# Main_module_scheme.net
KiCad netlist of a schematic drawn in EAGLE
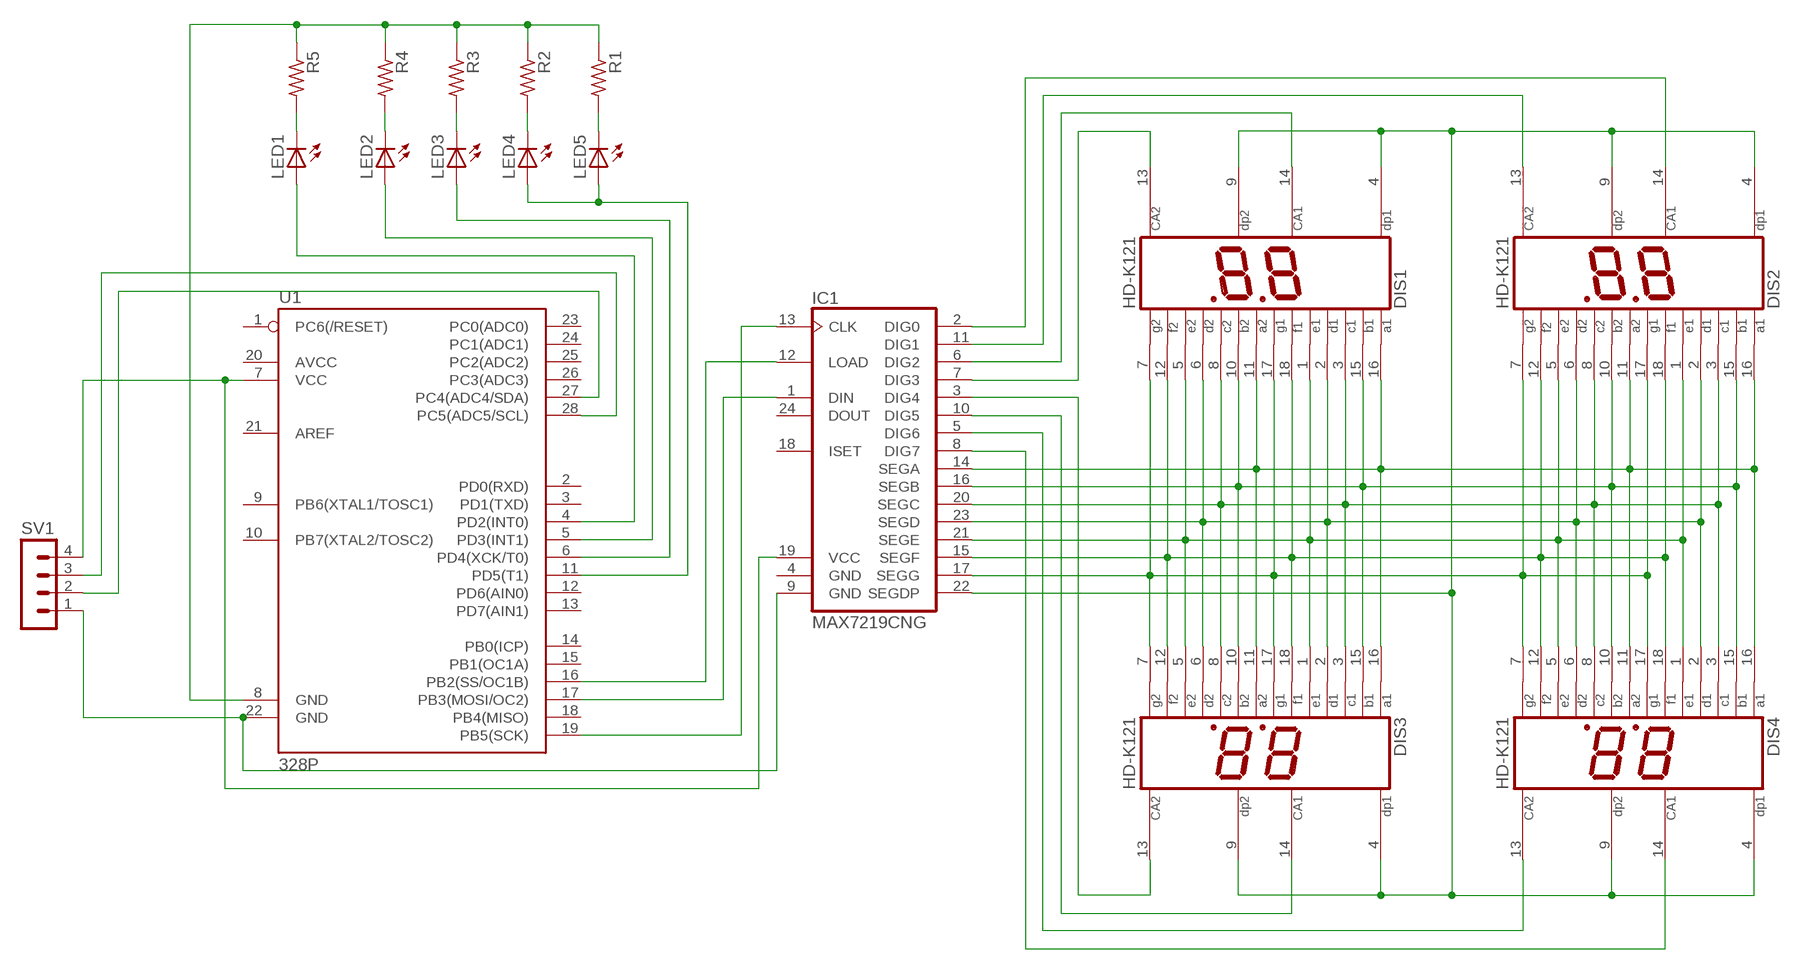
[diagram p0: schematic, sheet 1]

(export (version "E")
  (design (tool "Eeschema 10.0.6"))
  (components
    (comp (ref "DIS1")
      (value "HD-K121")
      (footprint "eagle-import:HDSP-R")
      (libsource (lib "eagle-import") (part "HD-K121"))
    )
    (comp (ref "DIS2")
      (value "HD-K121")
      (footprint "eagle-import:HDSP-R")
      (libsource (lib "eagle-import") (part "HD-K121"))
    )
    (comp (ref "DIS3")
      (value "HD-K121")
      (footprint "eagle-import:HDSP-R")
      (libsource (lib "eagle-import") (part "HD-K121"))
    )
    (comp (ref "DIS4")
      (value "HD-K121")
      (footprint "eagle-import:HDSP-R")
      (libsource (lib "eagle-import") (part "HD-K121"))
    )
    (comp (ref "IC1")
      (value "MAX7219CNG")
      (footprint "eagle-import:DIL24-3")
      (fields (field (name "MF") "MAXIM"))
      (libsource (lib "eagle-import") (part "MAX7219CNG"))
    )
    (comp (ref "LED1")
      (value "LED5MM")
      (footprint "eagle-import:LED5MM")
      (libsource (lib "eagle-import") (part "LED5MM"))
    )
    (comp (ref "LED2")
      (value "LED5MM")
      (footprint "eagle-import:LED5MM")
      (libsource (lib "eagle-import") (part "LED5MM"))
    )
    (comp (ref "LED3")
      (value "LED5MM")
      (footprint "eagle-import:LED5MM")
      (libsource (lib "eagle-import") (part "LED5MM"))
    )
    (comp (ref "LED4")
      (value "LED5MM")
      (footprint "eagle-import:LED5MM")
      (libsource (lib "eagle-import") (part "LED5MM"))
    )
    (comp (ref "LED5")
      (value "LED5MM")
      (footprint "eagle-import:LED5MM")
      (libsource (lib "eagle-import") (part "LED5MM"))
    )
    (comp (ref "R1")
      (value "FLIPFLOP-RES")
      (footprint "eagle-import:0805-THM")
      (libsource (lib "eagle-import") (part "FLIPFLOP-RES"))
    )
    (comp (ref "R2")
      (value "FLIPFLOP-RES")
      (footprint "eagle-import:0805-THM")
      (libsource (lib "eagle-import") (part "FLIPFLOP-RES"))
    )
    (comp (ref "R3")
      (value "FLIPFLOP-RES")
      (footprint "eagle-import:0805-THM")
      (libsource (lib "eagle-import") (part "FLIPFLOP-RES"))
    )
    (comp (ref "R4")
      (value "FLIPFLOP-RES")
      (footprint "eagle-import:0805-THM")
      (libsource (lib "eagle-import") (part "FLIPFLOP-RES"))
    )
    (comp (ref "R5")
      (value "FLIPFLOP-RES")
      (footprint "eagle-import:0805-THM")
      (libsource (lib "eagle-import") (part "FLIPFLOP-RES"))
    )
    (comp (ref "SV1")
      (value "MA04-1")
      (footprint "eagle-import:MA04-1")
      (libsource (lib "eagle-import") (part "MA04-1"))
    )
    (comp (ref "U1")
      (value "328P")
      (footprint "eagle-import:DIP28")
      (libsource (lib "eagle-import") (part "ATMEGA328P_PDIP"))
    )
  )
  (nets
    (net (code "1") (name "/GND") (class "Default")
      (node (ref "IC1") (pin "4") (pinfunction "GND_4") (pintype "power_in"))
    )
    (net (code "2") (name "Net-(DIS1-A1)") (class "Default")
      (node (ref "DIS1") (pin "11") (pinfunction "A2_11") (pintype "passive"))
      (node (ref "DIS1") (pin "16") (pinfunction "A1_16") (pintype "passive"))
      (node (ref "DIS2") (pin "11") (pinfunction "A2_11") (pintype "passive"))
      (node (ref "DIS2") (pin "16") (pinfunction "A1_16") (pintype "passive"))
      (node (ref "DIS3") (pin "11") (pinfunction "A2_11") (pintype "passive"))
      (node (ref "DIS3") (pin "16") (pinfunction "A1_16") (pintype "passive"))
      (node (ref "DIS4") (pin "11") (pinfunction "A2_11") (pintype "passive"))
      (node (ref "DIS4") (pin "16") (pinfunction "A1_16") (pintype "passive"))
      (node (ref "IC1") (pin "14") (pinfunction "SEGA_14") (pintype "output"))
    )
    (net (code "3") (name "Net-(DIS1-B1)") (class "Default")
      (node (ref "DIS1") (pin "10") (pinfunction "B2_10") (pintype "passive"))
      (node (ref "DIS1") (pin "15") (pinfunction "B1_15") (pintype "passive"))
      (node (ref "DIS2") (pin "10") (pinfunction "B2_10") (pintype "passive"))
      (node (ref "DIS2") (pin "15") (pinfunction "B1_15") (pintype "passive"))
      (node (ref "DIS3") (pin "10") (pinfunction "B2_10") (pintype "passive"))
      (node (ref "DIS3") (pin "15") (pinfunction "B1_15") (pintype "passive"))
      (node (ref "DIS4") (pin "10") (pinfunction "B2_10") (pintype "passive"))
      (node (ref "DIS4") (pin "15") (pinfunction "B1_15") (pintype "passive"))
      (node (ref "IC1") (pin "16") (pinfunction "SEGB_16") (pintype "output"))
    )
    (net (code "4") (name "Net-(DIS1-C1)") (class "Default")
      (node (ref "DIS1") (pin "3") (pinfunction "C1_3") (pintype "passive"))
      (node (ref "DIS1") (pin "8") (pinfunction "C2_8") (pintype "passive"))
      (node (ref "DIS2") (pin "3") (pinfunction "C1_3") (pintype "passive"))
      (node (ref "DIS2") (pin "8") (pinfunction "C2_8") (pintype "passive"))
      (node (ref "DIS3") (pin "3") (pinfunction "C1_3") (pintype "passive"))
      (node (ref "DIS3") (pin "8") (pinfunction "C2_8") (pintype "passive"))
      (node (ref "DIS4") (pin "3") (pinfunction "C1_3") (pintype "passive"))
      (node (ref "DIS4") (pin "8") (pinfunction "C2_8") (pintype "passive"))
      (node (ref "IC1") (pin "20") (pinfunction "SEGC_20") (pintype "output"))
    )
    (net (code "5") (name "Net-(DIS1-CA1)") (class "Default")
      (node (ref "DIS1") (pin "14") (pinfunction "CA1_14") (pintype "passive"))
      (node (ref "IC1") (pin "6") (pinfunction "DIG2_6") (pintype "output"))
    )
    (net (code "6") (name "Net-(DIS1-CA2)") (class "Default")
      (node (ref "DIS1") (pin "13") (pinfunction "CA2_13") (pintype "passive"))
      (node (ref "IC1") (pin "7") (pinfunction "DIG3_7") (pintype "output"))
    )
    (net (code "7") (name "Net-(DIS1-D1)") (class "Default")
      (node (ref "DIS1") (pin "2") (pinfunction "D1_2") (pintype "passive"))
      (node (ref "DIS1") (pin "6") (pinfunction "D2_6") (pintype "passive"))
      (node (ref "DIS2") (pin "2") (pinfunction "D1_2") (pintype "passive"))
      (node (ref "DIS2") (pin "6") (pinfunction "D2_6") (pintype "passive"))
      (node (ref "DIS3") (pin "2") (pinfunction "D1_2") (pintype "passive"))
      (node (ref "DIS3") (pin "6") (pinfunction "D2_6") (pintype "passive"))
      (node (ref "DIS4") (pin "2") (pinfunction "D1_2") (pintype "passive"))
      (node (ref "DIS4") (pin "6") (pinfunction "D2_6") (pintype "passive"))
      (node (ref "IC1") (pin "23") (pinfunction "SEGD_23") (pintype "output"))
    )
    (net (code "8") (name "Net-(DIS1-DP1)") (class "Default")
      (node (ref "DIS1") (pin "4") (pinfunction "DP1_4") (pintype "passive"))
      (node (ref "DIS1") (pin "9") (pinfunction "DP2_9") (pintype "passive"))
      (node (ref "DIS2") (pin "4") (pinfunction "DP1_4") (pintype "passive"))
      (node (ref "DIS2") (pin "9") (pinfunction "DP2_9") (pintype "passive"))
      (node (ref "DIS3") (pin "4") (pinfunction "DP1_4") (pintype "passive"))
      (node (ref "DIS3") (pin "9") (pinfunction "DP2_9") (pintype "passive"))
      (node (ref "DIS4") (pin "4") (pinfunction "DP1_4") (pintype "passive"))
      (node (ref "DIS4") (pin "9") (pinfunction "DP2_9") (pintype "passive"))
      (node (ref "IC1") (pin "22") (pinfunction "SEGDP_22") (pintype "output"))
    )
    (net (code "9") (name "Net-(DIS1-E1)") (class "Default")
      (node (ref "DIS1") (pin "1") (pinfunction "E1_1") (pintype "passive"))
      (node (ref "DIS1") (pin "5") (pinfunction "E2_5") (pintype "passive"))
      (node (ref "DIS2") (pin "1") (pinfunction "E1_1") (pintype "passive"))
      (node (ref "DIS2") (pin "5") (pinfunction "E2_5") (pintype "passive"))
      (node (ref "DIS3") (pin "1") (pinfunction "E1_1") (pintype "passive"))
      (node (ref "DIS3") (pin "5") (pinfunction "E2_5") (pintype "passive"))
      (node (ref "DIS4") (pin "1") (pinfunction "E1_1") (pintype "passive"))
      (node (ref "DIS4") (pin "5") (pinfunction "E2_5") (pintype "passive"))
      (node (ref "IC1") (pin "21") (pinfunction "SEGE_21") (pintype "output"))
    )
    (net (code "10") (name "Net-(DIS1-F1)") (class "Default")
      (node (ref "DIS1") (pin "12") (pinfunction "F2_12") (pintype "passive"))
      (node (ref "DIS1") (pin "18") (pinfunction "F1_18") (pintype "passive"))
      (node (ref "DIS2") (pin "12") (pinfunction "F2_12") (pintype "passive"))
      (node (ref "DIS2") (pin "18") (pinfunction "F1_18") (pintype "passive"))
      (node (ref "DIS3") (pin "12") (pinfunction "F2_12") (pintype "passive"))
      (node (ref "DIS3") (pin "18") (pinfunction "F1_18") (pintype "passive"))
      (node (ref "DIS4") (pin "12") (pinfunction "F2_12") (pintype "passive"))
      (node (ref "DIS4") (pin "18") (pinfunction "F1_18") (pintype "passive"))
      (node (ref "IC1") (pin "15") (pinfunction "SEGF_15") (pintype "output"))
    )
    (net (code "11") (name "Net-(DIS1-G1)") (class "Default")
      (node (ref "DIS1") (pin "17") (pinfunction "G1_17") (pintype "passive"))
      (node (ref "DIS1") (pin "7") (pinfunction "G2_7") (pintype "passive"))
      (node (ref "DIS2") (pin "17") (pinfunction "G1_17") (pintype "passive"))
      (node (ref "DIS2") (pin "7") (pinfunction "G2_7") (pintype "passive"))
      (node (ref "DIS3") (pin "17") (pinfunction "G1_17") (pintype "passive"))
      (node (ref "DIS3") (pin "7") (pinfunction "G2_7") (pintype "passive"))
      (node (ref "DIS4") (pin "17") (pinfunction "G1_17") (pintype "passive"))
      (node (ref "DIS4") (pin "7") (pinfunction "G2_7") (pintype "passive"))
      (node (ref "IC1") (pin "17") (pinfunction "SEGG_17") (pintype "output"))
    )
    (net (code "12") (name "Net-(DIS2-CA1)") (class "Default")
      (node (ref "DIS2") (pin "14") (pinfunction "CA1_14") (pintype "passive"))
      (node (ref "IC1") (pin "2") (pinfunction "DIG0_2") (pintype "output"))
    )
    (net (code "13") (name "Net-(DIS2-CA2)") (class "Default")
      (node (ref "DIS2") (pin "13") (pinfunction "CA2_13") (pintype "passive"))
      (node (ref "IC1") (pin "11") (pinfunction "DIG1_11") (pintype "output"))
    )
    (net (code "14") (name "Net-(DIS3-CA1)") (class "Default")
      (node (ref "DIS3") (pin "14") (pinfunction "CA1_14") (pintype "passive"))
      (node (ref "IC1") (pin "10") (pinfunction "DIG5_10") (pintype "output"))
    )
    (net (code "15") (name "Net-(DIS3-CA2)") (class "Default")
      (node (ref "DIS3") (pin "13") (pinfunction "CA2_13") (pintype "passive"))
      (node (ref "IC1") (pin "3") (pinfunction "DIG4_3") (pintype "output"))
    )
    (net (code "16") (name "Net-(DIS4-CA1)") (class "Default")
      (node (ref "DIS4") (pin "14") (pinfunction "CA1_14") (pintype "passive"))
      (node (ref "IC1") (pin "8") (pinfunction "DIG7_8") (pintype "output"))
    )
    (net (code "17") (name "Net-(DIS4-CA2)") (class "Default")
      (node (ref "DIS4") (pin "13") (pinfunction "CA2_13") (pintype "passive"))
      (node (ref "IC1") (pin "5") (pinfunction "DIG6_5") (pintype "output"))
    )
    (net (code "18") (name "Net-(IC1-CLK)") (class "Default")
      (node (ref "IC1") (pin "13") (pinfunction "CLK_13") (pintype "input"))
      (node (ref "U1") (pin "19") (pinfunction "PB5(SCK)_19") (pintype "bidirectional"))
    )
    (net (code "19") (name "Net-(IC1-DIN)") (class "Default")
      (node (ref "IC1") (pin "1") (pinfunction "DIN_1") (pintype "input"))
      (node (ref "U1") (pin "17") (pinfunction "PB3(MOSI/OC2)_17") (pintype "bidirectional"))
    )
    (net (code "20") (name "Net-(IC1-GND-Pad9)") (class "Default")
      (node (ref "IC1") (pin "9") (pinfunction "GND_9") (pintype "power_in"))
      (node (ref "SV1") (pin "1") (pinfunction "1_1") (pintype "passive"))
      (node (ref "U1") (pin "22") (pinfunction "GND_22") (pintype "bidirectional"))
    )
    (net (code "21") (name "Net-(IC1-LOAD)") (class "Default")
      (node (ref "IC1") (pin "12") (pinfunction "LOAD_12") (pintype "input"))
      (node (ref "U1") (pin "16") (pinfunction "PB2(SS/OC1B)_16") (pintype "bidirectional"))
    )
    (net (code "22") (name "Net-(IC1-VCC)") (class "Default")
      (node (ref "IC1") (pin "19") (pinfunction "VCC_19") (pintype "power_in"))
      (node (ref "SV1") (pin "4") (pinfunction "4_4") (pintype "passive"))
      (node (ref "U1") (pin "7") (pinfunction "VCC_7") (pintype "bidirectional"))
    )
    (net (code "23") (name "Net-(LED1-C)") (class "Default")
      (node (ref "LED1") (pin "K") (pinfunction "C_K") (pintype "passive"))
      (node (ref "R5") (pin "2") (pinfunction "2_2") (pintype "passive"))
    )
    (net (code "24") (name "Net-(LED2-C)") (class "Default")
      (node (ref "LED2") (pin "K") (pinfunction "C_K") (pintype "passive"))
      (node (ref "R4") (pin "2") (pinfunction "2_2") (pintype "passive"))
    )
    (net (code "25") (name "Net-(LED3-C)") (class "Default")
      (node (ref "LED3") (pin "K") (pinfunction "C_K") (pintype "passive"))
      (node (ref "R3") (pin "2") (pinfunction "2_2") (pintype "passive"))
    )
    (net (code "26") (name "Net-(LED4-C)") (class "Default")
      (node (ref "LED4") (pin "K") (pinfunction "C_K") (pintype "passive"))
      (node (ref "R2") (pin "2") (pinfunction "2_2") (pintype "passive"))
    )
    (net (code "27") (name "Net-(LED5-C)") (class "Default")
      (node (ref "LED5") (pin "K") (pinfunction "C_K") (pintype "passive"))
      (node (ref "R1") (pin "2") (pinfunction "2_2") (pintype "passive"))
    )
    (net (code "28") (name "Net-(R1-Pad1)") (class "Default")
      (node (ref "R1") (pin "1") (pinfunction "1_1") (pintype "passive"))
      (node (ref "R2") (pin "1") (pinfunction "1_1") (pintype "passive"))
      (node (ref "R3") (pin "1") (pinfunction "1_1") (pintype "passive"))
      (node (ref "R4") (pin "1") (pinfunction "1_1") (pintype "passive"))
      (node (ref "R5") (pin "1") (pinfunction "1_1") (pintype "passive"))
      (node (ref "U1") (pin "8") (pinfunction "GND_8") (pintype "bidirectional"))
    )
    (net (code "29") (name "Net-(U1-PC4(ADC4{slash}SDA))") (class "Default")
      (node (ref "SV1") (pin "2") (pinfunction "2_2") (pintype "passive"))
      (node (ref "U1") (pin "27") (pinfunction "PC4(ADC4/SDA)_27") (pintype "bidirectional"))
    )
    (net (code "30") (name "Net-(U1-PC5(ADC5{slash}SCL))") (class "Default")
      (node (ref "SV1") (pin "3") (pinfunction "3_3") (pintype "passive"))
      (node (ref "U1") (pin "28") (pinfunction "PC5(ADC5/SCL)_28") (pintype "bidirectional"))
    )
    (net (code "31") (name "Net-(U1-PD2(INT0))") (class "Default")
      (node (ref "LED1") (pin "A") (pinfunction "A_A") (pintype "passive"))
      (node (ref "U1") (pin "4") (pinfunction "PD2(INT0)_4") (pintype "bidirectional"))
    )
    (net (code "32") (name "Net-(U1-PD3(INT1))") (class "Default")
      (node (ref "LED2") (pin "A") (pinfunction "A_A") (pintype "passive"))
      (node (ref "U1") (pin "5") (pinfunction "PD3(INT1)_5") (pintype "bidirectional"))
    )
    (net (code "33") (name "Net-(U1-PD4(XCK{slash}T0))") (class "Default")
      (node (ref "LED3") (pin "A") (pinfunction "A_A") (pintype "passive"))
      (node (ref "U1") (pin "6") (pinfunction "PD4(XCK/T0)_6") (pintype "bidirectional"))
    )
    (net (code "34") (name "Net-(U1-PD5(T1))") (class "Default")
      (node (ref "LED4") (pin "A") (pinfunction "A_A") (pintype "passive"))
      (node (ref "LED5") (pin "A") (pinfunction "A_A") (pintype "passive"))
      (node (ref "U1") (pin "11") (pinfunction "PD5(T1)_11") (pintype "bidirectional"))
    )
    (net (code "35") (name "unconnected-(IC1-DOUT-Pad24)") (class "Default")
      (node (ref "IC1") (pin "24") (pinfunction "DOUT_24") (pintype "output"))
    )
    (net (code "36") (name "unconnected-(IC1-ISET-Pad18)") (class "Default")
      (node (ref "IC1") (pin "18") (pinfunction "ISET_18") (pintype "input"))
    )
    (net (code "37") (name "unconnected-(U1-AREF-Pad21)") (class "Default")
      (node (ref "U1") (pin "21") (pinfunction "AREF_21") (pintype "bidirectional"))
    )
    (net (code "38") (name "unconnected-(U1-AVCC-Pad20)") (class "Default")
      (node (ref "U1") (pin "20") (pinfunction "AVCC_20") (pintype "bidirectional"))
    )
    (net (code "39") (name "unconnected-(U1-PB0(ICP)-Pad14)") (class "Default")
      (node (ref "U1") (pin "14") (pinfunction "PB0(ICP)_14") (pintype "bidirectional"))
    )
    (net (code "40") (name "unconnected-(U1-PB1(OC1A)-Pad15)") (class "Default")
      (node (ref "U1") (pin "15") (pinfunction "PB1(OC1A)_15") (pintype "bidirectional"))
    )
    (net (code "41") (name "unconnected-(U1-PB4(MISO)-Pad18)") (class "Default")
      (node (ref "U1") (pin "18") (pinfunction "PB4(MISO)_18") (pintype "bidirectional"))
    )
    (net (code "42") (name "unconnected-(U1-PB6(XTAL1{slash}TOSC1)-Pad9)") (class "Default")
      (node (ref "U1") (pin "9") (pinfunction "PB6(XTAL1/TOSC1)_9") (pintype "bidirectional"))
    )
    (net (code "43") (name "unconnected-(U1-PB7(XTAL2{slash}TOSC2)-Pad10)") (class "Default")
      (node (ref "U1") (pin "10") (pinfunction "PB7(XTAL2/TOSC2)_10") (pintype "bidirectional"))
    )
    (net (code "44") (name "unconnected-(U1-PC0(ADC0)-Pad23)") (class "Default")
      (node (ref "U1") (pin "23") (pinfunction "PC0(ADC0)_23") (pintype "bidirectional"))
    )
    (net (code "45") (name "unconnected-(U1-PC1(ADC1)-Pad24)") (class "Default")
      (node (ref "U1") (pin "24") (pinfunction "PC1(ADC1)_24") (pintype "bidirectional"))
    )
    (net (code "46") (name "unconnected-(U1-PC2(ADC2)-Pad25)") (class "Default")
      (node (ref "U1") (pin "25") (pinfunction "PC2(ADC2)_25") (pintype "bidirectional"))
    )
    (net (code "47") (name "unconnected-(U1-PC3(ADC3)-Pad26)") (class "Default")
      (node (ref "U1") (pin "26") (pinfunction "PC3(ADC3)_26") (pintype "bidirectional"))
    )
    (net (code "48") (name "unconnected-(U1-PC6({slash}RESET)-Pad1)") (class "Default")
      (node (ref "U1") (pin "1") (pinfunction "PC6(/RESET)_1") (pintype "bidirectional"))
    )
    (net (code "49") (name "unconnected-(U1-PD0(RXD)-Pad2)") (class "Default")
      (node (ref "U1") (pin "2") (pinfunction "PD0(RXD)_2") (pintype "bidirectional"))
    )
    (net (code "50") (name "unconnected-(U1-PD1(TXD)-Pad3)") (class "Default")
      (node (ref "U1") (pin "3") (pinfunction "PD1(TXD)_3") (pintype "bidirectional"))
    )
    (net (code "51") (name "unconnected-(U1-PD6(AIN0)-Pad12)") (class "Default")
      (node (ref "U1") (pin "12") (pinfunction "PD6(AIN0)_12") (pintype "bidirectional"))
    )
    (net (code "52") (name "unconnected-(U1-PD7(AIN1)-Pad13)") (class "Default")
      (node (ref "U1") (pin "13") (pinfunction "PD7(AIN1)_13") (pintype "bidirectional"))
    )
  )
)
